# STM32F103RCT6.net
KiCad netlist of a schematic drawn in Altium Designer
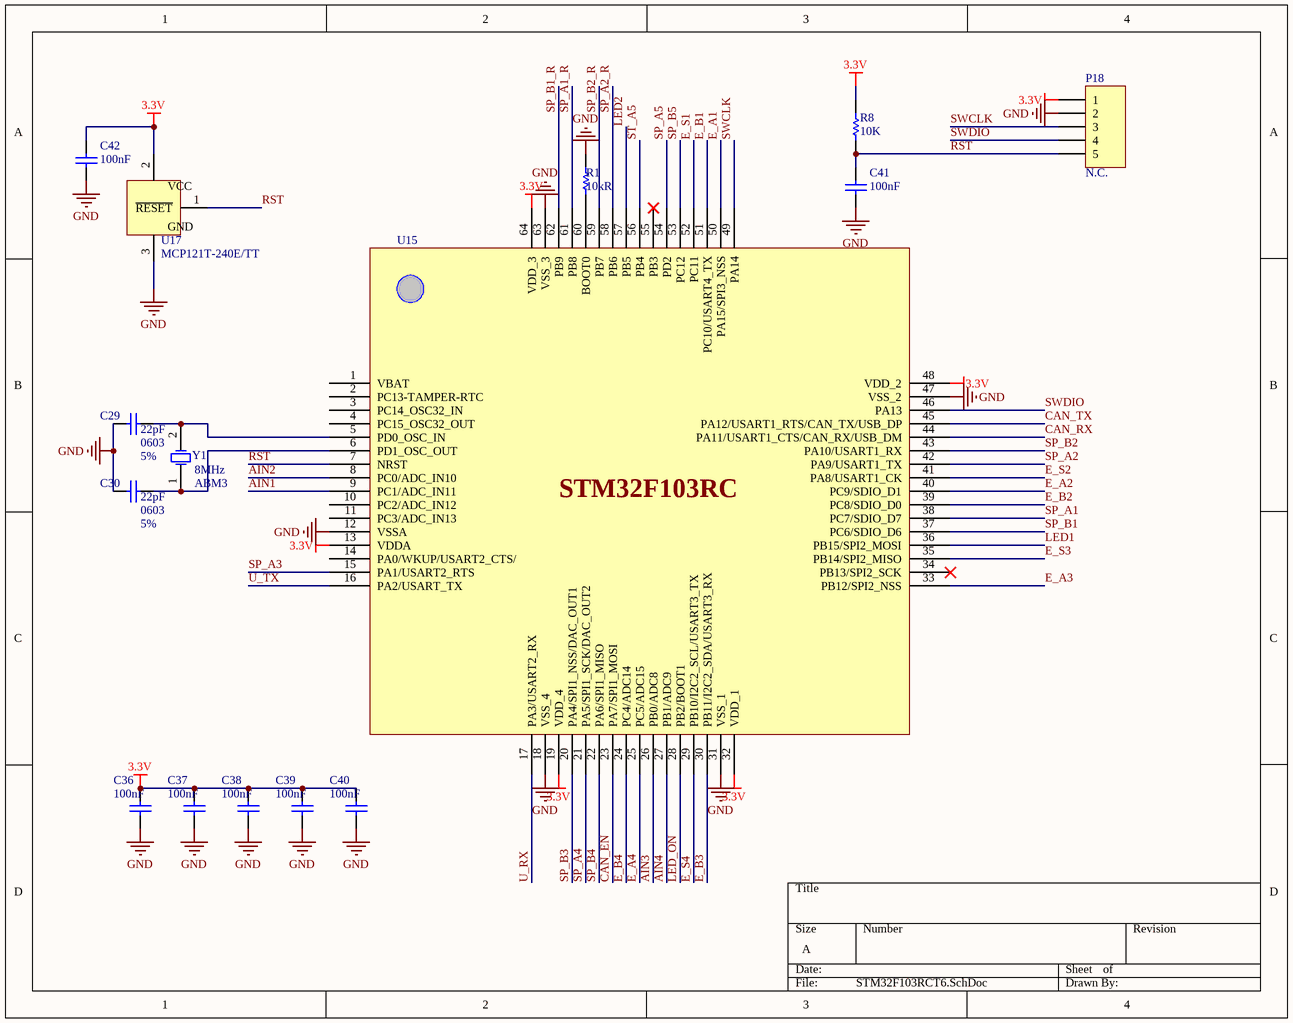
[diagram p0: STM32F103RCT6.SchDoc]

(export (version "E")
  (design (tool "Eeschema 10.0.6"))
  (components
    (comp (ref "C29")
      (value "22pF")
      (footprint "C0603")
      (description "CAP CER 22PF 50V C0G/NPO 0603")
      (fields
        (field (name "MANUFACTURER") "Yageo")
        (field (name "MANUFACTURER PART NUMBER") "CC0603JRNPO9BN220")
        (field (name "CASE CODE (IMPERIAL)") "0603")
        (field (name "TOLERANCE") "5%")
      )
      (libsource (lib "Miscellaneous Devices") (part "Cap_0603"))
    )
    (comp (ref "C30")
      (value "22pF")
      (footprint "C0603")
      (description "CAP CER 22PF 50V C0G/NPO 0603")
      (fields
        (field (name "MANUFACTURER") "Yageo")
        (field (name "MANUFACTURER PART NUMBER") "CC0603JRNPO9BN220")
        (field (name "CASE CODE (IMPERIAL)") "0603")
        (field (name "TOLERANCE") "5%")
      )
      (libsource (lib "Miscellaneous Devices") (part "Cap_0603"))
    )
    (comp (ref "C36")
      (value "100nF")
      (footprint "C0402")
      (description "100nF ±10% 16V X7R 0402 Multilayer Ceramic Capacitors MLCC - SMD/SMT RoHS")
      (fields
        (field (name "MANUFACTURER") "KEMET")
        (field (name "MANUFACTURER PART NUMBER") "C0402C104K4RAC-TU")
      )
      (libsource (lib "Miscellaneous Devices") (part "Cap"))
    )
    (comp (ref "C37")
      (value "100nF")
      (footprint "C0402")
      (description "100nF ±10% 16V X7R 0402 Multilayer Ceramic Capacitors MLCC - SMD/SMT RoHS")
      (fields
        (field (name "MANUFACTURER") "KEMET")
        (field (name "MANUFACTURER PART NUMBER") "C0402C104K4RAC-TU")
      )
      (libsource (lib "Miscellaneous Devices") (part "Cap"))
    )
    (comp (ref "C38")
      (value "100nF")
      (footprint "C0402")
      (description "100nF ±10% 16V X7R 0402 Multilayer Ceramic Capacitors MLCC - SMD/SMT RoHS")
      (fields
        (field (name "MANUFACTURER") "KEMET")
        (field (name "MANUFACTURER PART NUMBER") "C0402C104K4RAC-TU")
      )
      (libsource (lib "Miscellaneous Devices") (part "Cap"))
    )
    (comp (ref "C39")
      (value "100nF")
      (footprint "C0402")
      (description "100nF ±10% 16V X7R 0402 Multilayer Ceramic Capacitors MLCC - SMD/SMT RoHS")
      (fields
        (field (name "MANUFACTURER") "KEMET")
        (field (name "MANUFACTURER PART NUMBER") "C0402C104K4RAC-TU")
      )
      (libsource (lib "Miscellaneous Devices") (part "Cap"))
    )
    (comp (ref "C40")
      (value "100nF")
      (footprint "C0402")
      (description "100nF ±10% 16V X7R 0402 Multilayer Ceramic Capacitors MLCC - SMD/SMT RoHS")
      (fields
        (field (name "MANUFACTURER") "KEMET")
        (field (name "MANUFACTURER PART NUMBER") "C0402C104K4RAC-TU")
      )
      (libsource (lib "Miscellaneous Devices") (part "Cap"))
    )
    (comp (ref "C41")
      (value "100nF")
      (footprint "C0402")
      (description "100nF ±10% 16V X7R 0402 Multilayer Ceramic Capacitors MLCC - SMD/SMT RoHS")
      (fields
        (field (name "MANUFACTURER") "KEMET")
        (field (name "MANUFACTURER PART NUMBER") "C0402C104K4RAC-TU")
      )
      (libsource (lib "Miscellaneous Devices") (part "Cap"))
    )
    (comp (ref "C42")
      (value "100nF")
      (footprint "C0402")
      (description "100nF ±10% 16V X7R 0402 Multilayer Ceramic Capacitors MLCC - SMD/SMT RoHS")
      (fields
        (field (name "MANUFACTURER") "KEMET")
        (field (name "MANUFACTURER PART NUMBER") "C0402C104K4RAC-TU")
      )
      (libsource (lib "Miscellaneous Devices") (part "Cap"))
    )
    (comp (ref "P18")
      (value "N.C.")
      (footprint "HDR1X5")
      (description "Header, 5-Pin")
      (libsource (lib "Miscellaneous Connectors") (part "Header 5"))
    )
    (comp (ref "R1")
      (value "10kR")
      (footprint "R0402")
      (description "SMD Chip Resistor, 10 kOhm, ± 5%, 63 mW, 0402 [1005 Metric], Thick Film, General Purpose")
      (fields
        (field (name "MANUFACTURER") "Yageo")
        (field (name "MANUFACTURER PART NUMBER") "RC0402JR-0710KL")
      )
      (libsource (lib "Miscellaneous Devices") (part "Res1"))
    )
    (comp (ref "R8")
      (value "10K")
      (footprint "R0402")
      (description "RES SMD 10 KOHM 1% 1/16W 0402")
      (fields (field (name "Comment") "Res1"))
      (libsource (lib "Miscellaneous Devices") (part "Res1"))
    )
    (comp (ref "U15")
      (value "STM32F103RC")
      (footprint "LQFP64")
      (description "MCU 32-bit STM32F1 ARM Cortex M3 RISC 256KB Flash 2.5V/3.3V 64-Pin LQFP Tray")
      (fields
        (field (name "MANUFACTURER") "STMicroelectronics")
        (field (name "MANUFACTURER PART NUMBER") "STM32F103RCT6")
      )
      (libsource (lib "STM32F103RC") (part "STM32F103RC"))
    )
    (comp (ref "U17")
      (value "MCP121T-240E/TT")
      (footprint "SOT23-3")
      (description "IC SUPERVISOR 1 CHANNEL SOT23-3")
      (fields (field (name "MANUFACTURER") "Microchip"))
      (libsource (lib "Schlib1") (part "MCP121"))
    )
    (comp (ref "Y1")
      (value "8MHz")
      (footprint "ABM3")
      (description "CRYSTAL 8.0000MHZ 12PF SMD")
      (fields
        (field (name "MANUFACTURER") "Kyocera AVX")
        (field (name "MANUFACTURER PART NUMBER") "CX5032GB08000H0HPQZ1")
        (field (name "CASE/PACKAGE") "ABM3")
      )
      (libsource (lib "Miscellaneous Devices") (part "XTAL"))
    )
  )
  (nets
    (net (code "1") (name "/AIN1") (class "Default")
      (node (ref "U15") (pin "9") (pinfunction "PC1/ADC_IN11_9") (pintype "passive"))
    )
    (net (code "2") (name "/AIN2") (class "Default")
      (node (ref "U15") (pin "8") (pinfunction "PC0/ADC_IN10_8") (pintype "passive"))
    )
    (net (code "3") (name "/AIN3") (class "Default")
      (node (ref "U15") (pin "26") (pinfunction "PB0/ADC8_26") (pintype "passive"))
    )
    (net (code "4") (name "/AIN4") (class "Default")
      (node (ref "U15") (pin "27") (pinfunction "PB1/ADC9_27") (pintype "passive"))
    )
    (net (code "5") (name "/CAN_EN") (class "Default")
      (node (ref "U15") (pin "23") (pinfunction "PA7/SPI1_MOSI_23") (pintype "passive"))
    )
    (net (code "6") (name "/CAN_RX") (class "Default")
      (node (ref "U15") (pin "44") (pinfunction "PA11/USART1_CTS/CAN_RX/USB_DM_44") (pintype "passive"))
    )
    (net (code "7") (name "/CAN_TX") (class "Default")
      (node (ref "U15") (pin "45") (pinfunction "PA12/USART1_RTS/CAN_TX/USB_DP_45") (pintype "passive"))
    )
    (net (code "8") (name "/E_A1") (class "Default")
      (node (ref "U15") (pin "50") (pinfunction "PA15/SPI3_NSS_50") (pintype "passive"))
    )
    (net (code "9") (name "/E_A2") (class "Default")
      (node (ref "U15") (pin "40") (pinfunction "PC9/SDIO_D1_40") (pintype "passive"))
    )
    (net (code "10") (name "/E_A3") (class "Default")
      (node (ref "U15") (pin "33") (pinfunction "PB12/SPI2_NSS_33") (pintype "passive"))
    )
    (net (code "11") (name "/E_A4") (class "Default")
      (node (ref "U15") (pin "25") (pinfunction "PC5/ADC15_25") (pintype "passive"))
    )
    (net (code "12") (name "/E_B1") (class "Default")
      (node (ref "U15") (pin "51") (pinfunction "PC10/USART4_TX_51") (pintype "passive"))
    )
    (net (code "13") (name "/E_B2") (class "Default")
      (node (ref "U15") (pin "39") (pinfunction "PC8/SDIO_D0_39") (pintype "passive"))
    )
    (net (code "14") (name "/E_B3") (class "Default")
      (node (ref "U15") (pin "30") (pinfunction "PB11/I2C2_SDA/USART3_RX_30") (pintype "passive"))
    )
    (net (code "15") (name "/E_B4") (class "Default")
      (node (ref "U15") (pin "24") (pinfunction "PC4/ADC14_24") (pintype "passive"))
    )
    (net (code "16") (name "/E_S1") (class "Default")
      (node (ref "U15") (pin "52") (pinfunction "PC11_52") (pintype "passive"))
    )
    (net (code "17") (name "/E_S2") (class "Default")
      (node (ref "U15") (pin "41") (pinfunction "PA8/USART1_CK_41") (pintype "passive"))
    )
    (net (code "18") (name "/E_S3") (class "Default")
      (node (ref "U15") (pin "35") (pinfunction "PB14/SPI2_MISO_35") (pintype "passive"))
    )
    (net (code "19") (name "/E_S4") (class "Default")
      (node (ref "U15") (pin "29") (pinfunction "PB10/I2C2_SCL/USART3_TX_29") (pintype "passive"))
    )
    (net (code "20") (name "/LED1") (class "Default")
      (node (ref "U15") (pin "36") (pinfunction "PB15/SPI2_MOSI_36") (pintype "passive"))
    )
    (net (code "21") (name "/LED2") (class "Default")
      (node (ref "U15") (pin "57") (pinfunction "PB5_57") (pintype "passive"))
    )
    (net (code "22") (name "/LED_ON") (class "Default")
      (node (ref "U15") (pin "28") (pinfunction "PB2/BOOT1_28") (pintype "passive"))
    )
    (net (code "23") (name "/RST") (class "Default")
      (node (ref "C41") (pin "2") (pinfunction "2_2") (pintype "passive"))
      (node (ref "P18") (pin "5") (pinfunction "5_5") (pintype "passive"))
      (node (ref "R8") (pin "2") (pinfunction "2_2") (pintype "passive"))
      (node (ref "U15") (pin "7") (pinfunction "NRST_7") (pintype "passive"))
      (node (ref "U17") (pin "1") (pinfunction "RESET_1") (pintype "passive"))
    )
    (net (code "24") (name "/SP_A1") (class "Default")
      (node (ref "U15") (pin "38") (pinfunction "PC7/SDIO_D7_38") (pintype "passive"))
    )
    (net (code "25") (name "/SP_A1_R") (class "Default")
      (node (ref "U15") (pin "61") (pinfunction "PB8_61") (pintype "passive"))
    )
    (net (code "26") (name "/SP_A2") (class "Default")
      (node (ref "U15") (pin "42") (pinfunction "PA9/USART1_TX_42") (pintype "passive"))
    )
    (net (code "27") (name "/SP_A2_R") (class "Default")
      (node (ref "U15") (pin "58") (pinfunction "PB6_58") (pintype "passive"))
    )
    (net (code "28") (name "/SP_A3") (class "Default")
      (node (ref "U15") (pin "15") (pinfunction "PA1/USART2_RTS_15") (pintype "passive"))
    )
    (net (code "29") (name "/SP_A4") (class "Default")
      (node (ref "U15") (pin "21") (pinfunction "PA5/SPI1_SCK/DAC_OUT2_21") (pintype "passive"))
    )
    (net (code "30") (name "/SP_A5") (class "Default")
      (node (ref "U15") (pin "54") (pinfunction "PD2_54") (pintype "passive"))
    )
    (net (code "31") (name "/SP_B1") (class "Default")
      (node (ref "U15") (pin "37") (pinfunction "PC6/SDIO_D6_37") (pintype "passive"))
    )
    (net (code "32") (name "/SP_B1_R") (class "Default")
      (node (ref "U15") (pin "62") (pinfunction "PB9_62") (pintype "passive"))
    )
    (net (code "33") (name "/SP_B2") (class "Default")
      (node (ref "U15") (pin "43") (pinfunction "PA10/USART1_RX_43") (pintype "passive"))
    )
    (net (code "34") (name "/SP_B2_R") (class "Default")
      (node (ref "U15") (pin "59") (pinfunction "PB7_59") (pintype "passive"))
    )
    (net (code "35") (name "/SP_B3") (class "Default")
      (node (ref "U15") (pin "20") (pinfunction "PA4/SPI1_NSS/DAC_OUT1_20") (pintype "passive"))
    )
    (net (code "36") (name "/SP_B4") (class "Default")
      (node (ref "U15") (pin "22") (pinfunction "PA6/SPI1_MISO_22") (pintype "passive"))
    )
    (net (code "37") (name "/SP_B5") (class "Default")
      (node (ref "U15") (pin "53") (pinfunction "PC12_53") (pintype "passive"))
    )
    (net (code "38") (name "/ST_A5") (class "Default")
      (node (ref "U15") (pin "56") (pinfunction "PB4_56") (pintype "passive"))
    )
    (net (code "39") (name "/SWCLK") (class "Default")
      (node (ref "P18") (pin "3") (pinfunction "3_3") (pintype "passive"))
      (node (ref "U15") (pin "49") (pinfunction "PA14_49") (pintype "passive"))
    )
    (net (code "40") (name "/SWDIO") (class "Default")
      (node (ref "P18") (pin "4") (pinfunction "4_4") (pintype "passive"))
      (node (ref "U15") (pin "46") (pinfunction "PA13_46") (pintype "passive"))
    )
    (net (code "41") (name "/U_RX") (class "Default")
      (node (ref "U15") (pin "17") (pinfunction "PA3/USART2_RX_17") (pintype "passive"))
    )
    (net (code "42") (name "/U_TX") (class "Default")
      (node (ref "U15") (pin "16") (pinfunction "PA2/USART_TX_16") (pintype "passive"))
    )
    (net (code "43") (name "3.3V") (class "Default")
      (node (ref "C36") (pin "2") (pinfunction "2_2") (pintype "passive"))
      (node (ref "C37") (pin "2") (pinfunction "2_2") (pintype "passive"))
      (node (ref "C38") (pin "2") (pinfunction "2_2") (pintype "passive"))
      (node (ref "C39") (pin "2") (pinfunction "2_2") (pintype "passive"))
      (node (ref "C40") (pin "2") (pinfunction "2_2") (pintype "passive"))
      (node (ref "C42") (pin "2") (pinfunction "2_2") (pintype "passive"))
      (node (ref "P18") (pin "1") (pinfunction "1_1") (pintype "passive"))
      (node (ref "R8") (pin "1") (pinfunction "1_1") (pintype "passive"))
      (node (ref "U15") (pin "13") (pinfunction "VDDA_13") (pintype "passive"))
      (node (ref "U15") (pin "19") (pinfunction "VDD_4_19") (pintype "passive"))
      (node (ref "U15") (pin "32") (pinfunction "VDD_1_32") (pintype "passive"))
      (node (ref "U15") (pin "48") (pinfunction "VDD_2_48") (pintype "passive"))
      (node (ref "U15") (pin "64") (pinfunction "VDD_3_64") (pintype "passive"))
      (node (ref "U17") (pin "2") (pinfunction "VCC_2") (pintype "passive"))
    )
    (net (code "44") (name "GND") (class "Default")
      (node (ref "C29") (pin "2") (pinfunction "2_2") (pintype "passive"))
      (node (ref "C30") (pin "2") (pinfunction "2_2") (pintype "passive"))
      (node (ref "C36") (pin "1") (pinfunction "1_1") (pintype "passive"))
      (node (ref "C37") (pin "1") (pinfunction "1_1") (pintype "passive"))
      (node (ref "C38") (pin "1") (pinfunction "1_1") (pintype "passive"))
      (node (ref "C39") (pin "1") (pinfunction "1_1") (pintype "passive"))
      (node (ref "C40") (pin "1") (pinfunction "1_1") (pintype "passive"))
      (node (ref "C41") (pin "1") (pinfunction "1_1") (pintype "passive"))
      (node (ref "C42") (pin "1") (pinfunction "1_1") (pintype "passive"))
      (node (ref "P18") (pin "2") (pinfunction "2_2") (pintype "passive"))
      (node (ref "R1") (pin "2") (pinfunction "2_2") (pintype "passive"))
      (node (ref "U15") (pin "12") (pinfunction "VSSA_12") (pintype "passive"))
      (node (ref "U15") (pin "18") (pinfunction "VSS_4_18") (pintype "passive"))
      (node (ref "U15") (pin "31") (pinfunction "VSS_1_31") (pintype "passive"))
      (node (ref "U15") (pin "47") (pinfunction "VSS_2_47") (pintype "passive"))
      (node (ref "U15") (pin "63") (pinfunction "VSS_3_63") (pintype "passive"))
      (node (ref "U17") (pin "3") (pinfunction "GND_3") (pintype "passive"))
    )
    (net (code "45") (name "Net-(U15-BOOT0)") (class "Default")
      (node (ref "R1") (pin "1") (pinfunction "1_1") (pintype "passive"))
      (node (ref "U15") (pin "60") (pinfunction "BOOT0_60") (pintype "passive"))
    )
    (net (code "46") (name "Net-(U15-PD0_OSC_IN)") (class "Default")
      (node (ref "C29") (pin "1") (pinfunction "1_1") (pintype "passive"))
      (node (ref "U15") (pin "5") (pinfunction "PD0_OSC_IN_5") (pintype "passive"))
      (node (ref "Y1") (pin "2") (pinfunction "OSC2_2") (pintype "passive"))
    )
    (net (code "47") (name "Net-(U15-PD1_OSC_OUT)") (class "Default")
      (node (ref "C30") (pin "1") (pinfunction "1_1") (pintype "passive"))
      (node (ref "U15") (pin "6") (pinfunction "PD1_OSC_OUT_6") (pintype "passive"))
      (node (ref "Y1") (pin "1") (pinfunction "OSC1_1") (pintype "passive"))
    )
    (net (code "48") (name "unconnected-(U15-PA0{slash}WKUP{slash}USART2_CTS{slash}-Pad14)") (class "Default")
      (node (ref "U15") (pin "14") (pinfunction "PA0/WKUP/USART2_CTS/_14") (pintype "passive"))
    )
    (net (code "49") (name "unconnected-(U15-PB3-Pad55)") (class "Default")
      (node (ref "U15") (pin "55") (pinfunction "PB3_55") (pintype "passive+no_connect"))
    )
    (net (code "50") (name "unconnected-(U15-PB13{slash}SPI2_SCK-Pad34)") (class "Default")
      (node (ref "U15") (pin "34") (pinfunction "PB13/SPI2_SCK_34") (pintype "passive+no_connect"))
    )
    (net (code "51") (name "unconnected-(U15-PC2{slash}ADC_IN12-Pad10)") (class "Default")
      (node (ref "U15") (pin "10") (pinfunction "PC2/ADC_IN12_10") (pintype "passive"))
    )
    (net (code "52") (name "unconnected-(U15-PC3{slash}ADC_IN13-Pad11)") (class "Default")
      (node (ref "U15") (pin "11") (pinfunction "PC3/ADC_IN13_11") (pintype "passive"))
    )
    (net (code "53") (name "unconnected-(U15-PC13-TAMPER-RTC-Pad2)") (class "Default")
      (node (ref "U15") (pin "2") (pinfunction "PC13-TAMPER-RTC_2") (pintype "passive"))
    )
    (net (code "54") (name "unconnected-(U15-PC14_OSC32_IN-Pad3)") (class "Default")
      (node (ref "U15") (pin "3") (pinfunction "PC14_OSC32_IN_3") (pintype "passive"))
    )
    (net (code "55") (name "unconnected-(U15-PC15_OSC32_OUT-Pad4)") (class "Default")
      (node (ref "U15") (pin "4") (pinfunction "PC15_OSC32_OUT_4") (pintype "passive"))
    )
    (net (code "56") (name "unconnected-(U15-VBAT-Pad1)") (class "Default")
      (node (ref "U15") (pin "1") (pinfunction "VBAT_1") (pintype "passive"))
    )
  )
)
